# GP_ESP32_Circuit_Sheet.net
KiCad netlist of a schematic drawn in Altium Designer
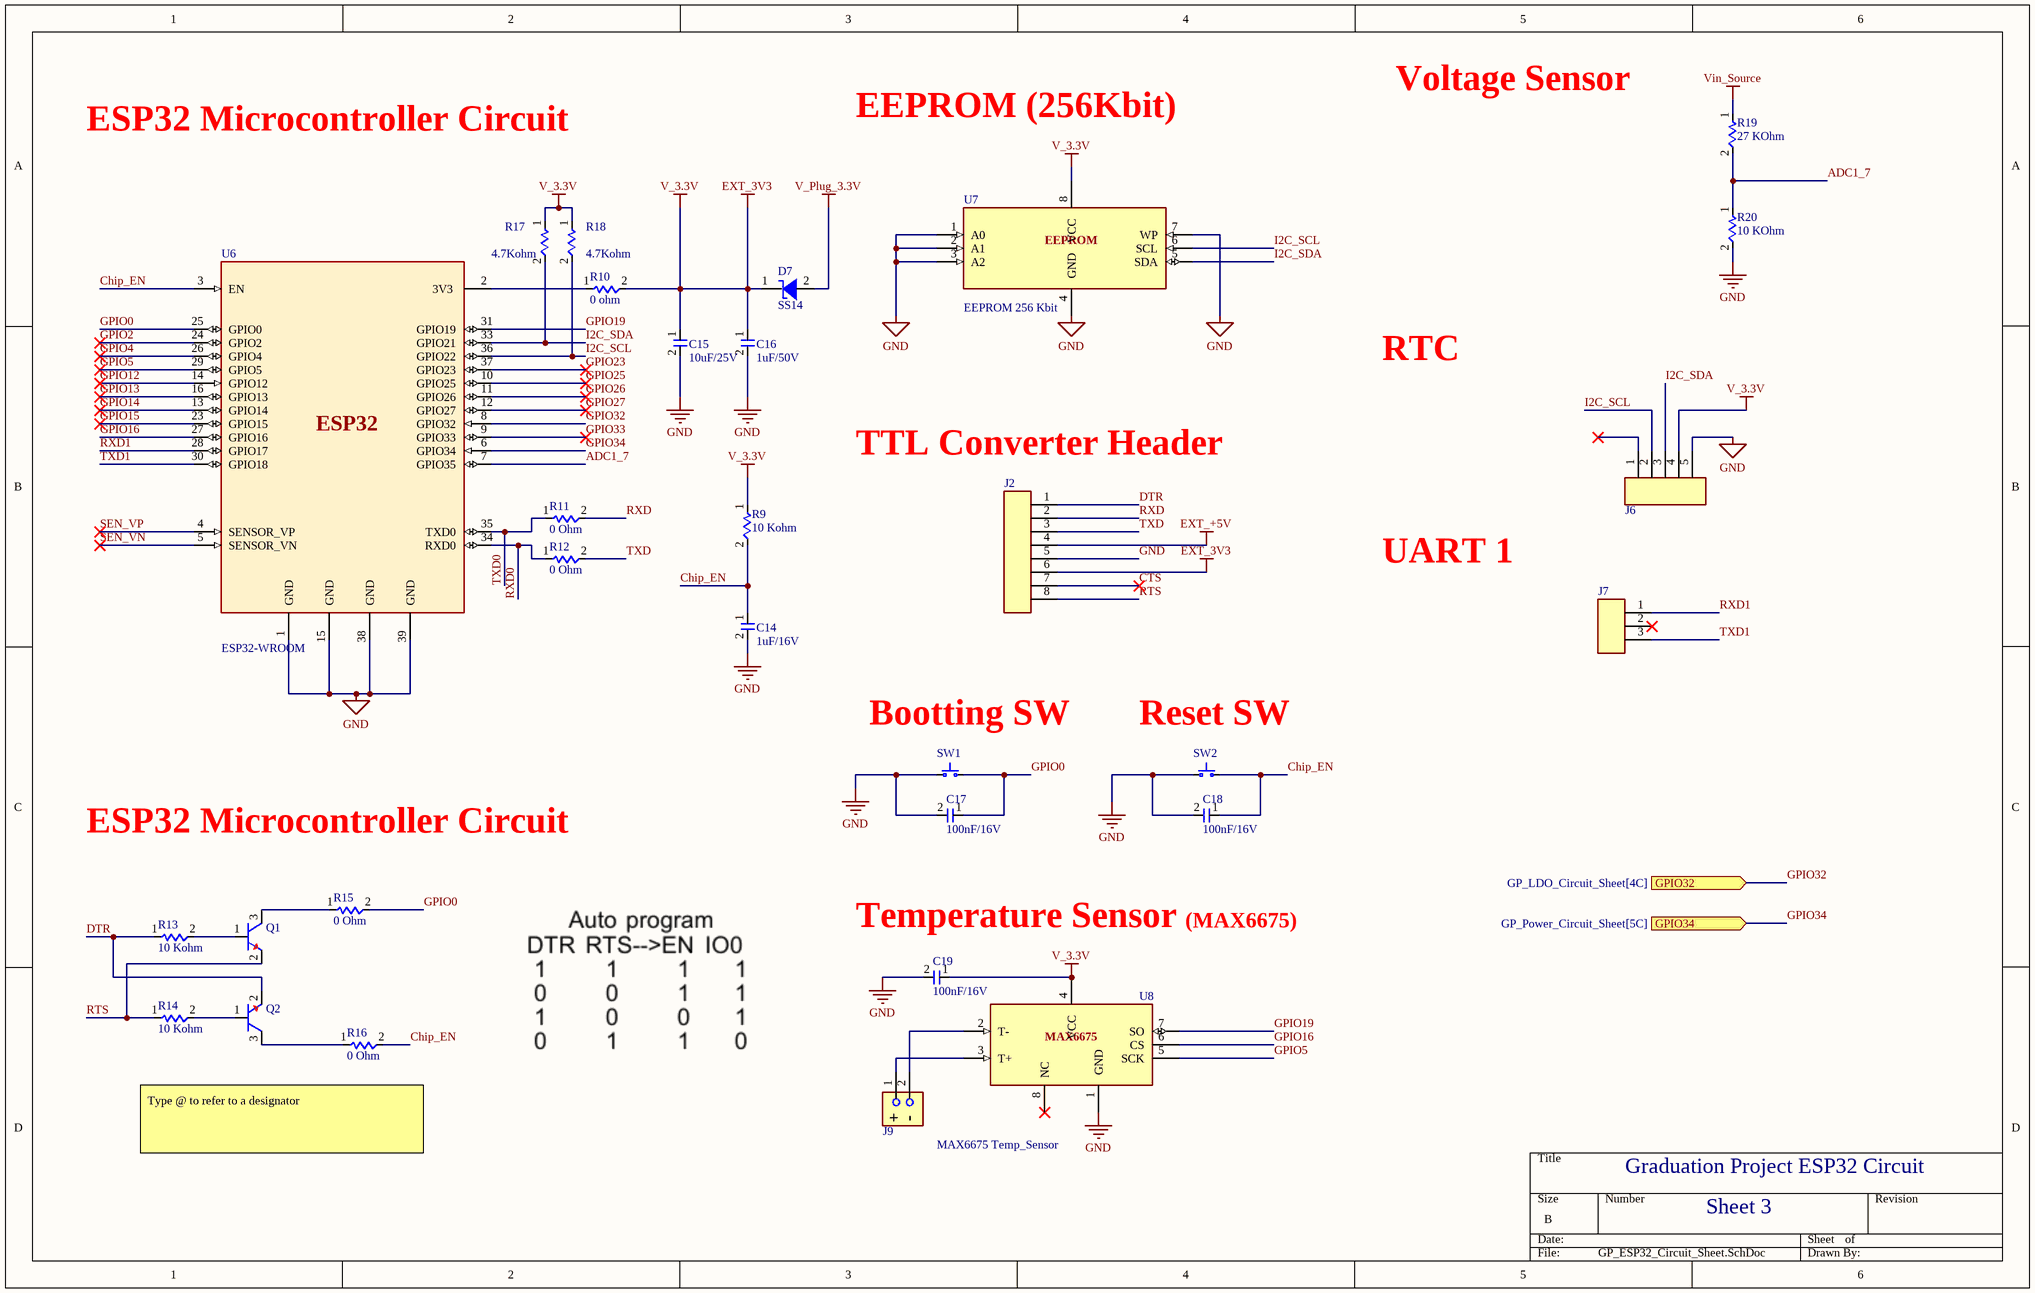
[diagram p0: GP_ESP32_Circuit_Sheet.SchDoc]

(export (version "E")
  (design (tool "Eeschema 10.0.6"))
  (components
    (comp (ref "C14")
      (value "1uF/16V")
      (footprint "Capacitor 100nF")
      (description "Ceramic Capacitor (100nF , 50V) SMD (1206)")
      (libsource (lib "GP_Integrated_Library") (part "Capacitor 100nF"))
    )
    (comp (ref "C15")
      (value "10uF/25V")
      (footprint "Capacitor 100nF")
      (description "Ceramic Capacitor (100nF , 50V) SMD (1206)")
      (libsource (lib "GP_Integrated_Library") (part "Capacitor 100nF"))
    )
    (comp (ref "C16")
      (value "1uF/50V")
      (footprint "Capacitor 100nF")
      (description "Ceramic Capacitor (100nF , 50V) SMD (1206)")
      (libsource (lib "GP_Integrated_Library") (part "Capacitor 100nF"))
    )
    (comp (ref "C17")
      (value "100nF/16V")
      (footprint "Capacitor 100nF")
      (description "Ceramic Capacitor (100nF , 50V) SMD (1206)")
      (libsource (lib "GP_Integrated_Library") (part "Capacitor 100nF"))
    )
    (comp (ref "C18")
      (value "100nF/16V")
      (footprint "Capacitor 100nF")
      (description "Ceramic Capacitor (100nF , 50V) SMD (1206)")
      (libsource (lib "GP_Integrated_Library") (part "Capacitor 100nF"))
    )
    (comp (ref "C19")
      (value "100nF/16V")
      (footprint "Capacitor 100nF")
      (description "Ceramic Capacitor (100nF , 50V) SMD (1206)")
      (libsource (lib "GP_Integrated_Library") (part "Capacitor 100nF"))
    )
    (comp (ref "D7")
      (value "SS14")
      (footprint "Schottky SS14")
      (description "SMD Schottky diode 5A 40V 1N5824 SS54 DO-214AB SMC")
      (libsource (lib "GP_Integrated_Library") (part "Schottky SS14"))
    )
    (comp (ref "J2")
      (value "Pin Header 1x8")
      (footprint "Pin Header 1x8")
      (description "Pin Header male (2.54mm) 1X40 Straight Long (20 CM)")
      (libsource (lib "GP_Integrated_Library") (part "Pin Header 1x8"))
    )
    (comp (ref "J6")
      (value "Pin Header 1x5")
      (footprint "Header Pin 1x5")
      (description "Pin Header male (2.54mm) 1X40 Straight Long (20 CM)")
      (libsource (lib "GP_Integrated_Library") (part "Pin Header 1x5"))
    )
    (comp (ref "J7")
      (value "Pin Header 1x2")
      (footprint "Header Pin 1x3")
      (description "Pin Header male (2.54mm) 1X40 Straight Long (20 CM)")
      (libsource (lib "GP_Integrated_Library") (part "Pin Header 1x2"))
    )
    (comp (ref "J9")
      (value "terminal block connector")
      (footprint "Battery Connector")
      (description "2-Pole 5mm Pitch PCB Mount Screw TermInal Block 8A 250V")
      (libsource (lib "GP_Integrated_Library") (part "Terminal Block"))
    )
    (comp (ref "Q1")
      (value "Transistor npn")
      (footprint "Transistor npn")
      (description "0.6A , 75V , NPN General Purpose Transistor .(SOT-23)")
      (libsource (lib "GP_Integrated_Library") (part "Transistor npn"))
    )
    (comp (ref "Q2")
      (value "Transistor npn")
      (footprint "Transistor npn")
      (description "0.6A , 75V , NPN General Purpose Transistor .(SOT-23)")
      (libsource (lib "GP_Integrated_Library") (part "Transistor npn"))
    )
    (comp (ref "R9")
      (value "10 Kohm")
      (footprint "Resistor 4.7KKohm")
      (description "SMD RESISTORS 200V-500V 1206 ? 5% tolerance")
      (libsource (lib "GP_Integrated_Library") (part "Resistor 10 Kohm"))
    )
    (comp (ref "R10")
      (value "0 ohm")
      (footprint "Resistor 4.7KKohm")
      (description "SMD Resistor (220 ohm , 1/4W)")
      (libsource (lib "GP_Integrated_Library") (part "Resistor 4.7Kohm"))
    )
    (comp (ref "R11")
      (value "0 Ohm")
      (footprint "Resistor 0.050ohm")
      (description "2512 SMD Alloy Power Shunt Resistors 1W 6.4×3.2mm 0.050 Ohm ( SMD Marking R050)")
      (libsource (lib "GP_Integrated_Library") (part "Resistor 0.050 Ohm"))
    )
    (comp (ref "R12")
      (value "0 Ohm")
      (footprint "Resistor 0.050ohm")
      (description "2512 SMD Alloy Power Shunt Resistors 1W 6.4×3.2mm 0.050 Ohm ( SMD Marking R050)")
      (libsource (lib "GP_Integrated_Library") (part "Resistor 0.050 Ohm"))
    )
    (comp (ref "R13")
      (value "10 Kohm")
      (footprint "Resistor 4.7KKohm")
      (description "SMD RESISTORS 200V-500V 1206 ? 5% tolerance")
      (libsource (lib "GP_Integrated_Library") (part "Resistor 10 Kohm"))
    )
    (comp (ref "R14")
      (value "10 Kohm")
      (footprint "Resistor 4.7KKohm")
      (description "SMD RESISTORS 200V-500V 1206 ? 5% tolerance")
      (libsource (lib "GP_Integrated_Library") (part "Resistor 10 Kohm"))
    )
    (comp (ref "R15")
      (value "0 Ohm")
      (footprint "Resistor 0.050ohm")
      (description "2512 SMD Alloy Power Shunt Resistors 1W 6.4×3.2mm 0.050 Ohm ( SMD Marking R050)")
      (libsource (lib "GP_Integrated_Library") (part "Resistor 0.050 Ohm"))
    )
    (comp (ref "R16")
      (value "0 Ohm")
      (footprint "Resistor 0.050ohm")
      (description "2512 SMD Alloy Power Shunt Resistors 1W 6.4×3.2mm 0.050 Ohm ( SMD Marking R050)")
      (libsource (lib "GP_Integrated_Library") (part "Resistor 0.050 Ohm"))
    )
    (comp (ref "R17")
      (value "4.7Kohm")
      (footprint "Resistor 4.7KKohm")
      (description "SMD Resistor (220 ohm , 1/4W)")
      (libsource (lib "GP_Integrated_Library") (part "Resistor 4.7Kohm"))
    )
    (comp (ref "R18")
      (value "4.7Kohm")
      (footprint "Resistor 4.7KKohm")
      (description "SMD Resistor (220 ohm , 1/4W)")
      (libsource (lib "GP_Integrated_Library") (part "Resistor 4.7Kohm"))
    )
    (comp (ref "R19")
      (value "27 KOhm")
      (footprint "Resistor 0.050ohm")
      (description "2512 SMD Alloy Power Shunt Resistors 1W 6.4×3.2mm 0.050 Ohm ( SMD Marking R050)")
      (libsource (lib "GP_Integrated_Library") (part "Resistor 0.050 Ohm"))
    )
    (comp (ref "R20")
      (value "10 KOhm")
      (footprint "Resistor 0.050ohm")
      (description "2512 SMD Alloy Power Shunt Resistors 1W 6.4×3.2mm 0.050 Ohm ( SMD Marking R050)")
      (libsource (lib "GP_Integrated_Library") (part "Resistor 0.050 Ohm"))
    )
    (comp (ref "SW1")
      (value "Push Button")
      (footprint "Push Button")
      (description "PCB Press 2pin (6X6) 100K cycles\r\nMomentary Push Button Tact Tactile Switch")
      (libsource (lib "GP_Integrated_Library") (part "Push Button"))
    )
    (comp (ref "SW2")
      (value "Push Button")
      (footprint "Push Button")
      (description "PCB Press 2pin (6X6) 100K cycles\r\nMomentary Push Button Tact Tactile Switch")
      (libsource (lib "GP_Integrated_Library") (part "Push Button"))
    )
    (comp (ref "U6")
      (value "ESP32-WROOM")
      (footprint "ESP32")
      (description "Bluetooth, WiFi 802.11b/g/n, Bluetooth v5.0 Transceiver Module 2.4GHz PCB Trace Surface Mount")
      (libsource (lib "GP_Integrated_Library") (part "ESP32-WROOM"))
    )
    (comp (ref "U7")
      (value "EEPROM 256 Kbit")
      (footprint "EEPROM")
      (description "I2C-Compatible, (2-Wire) Serial EEPROM 256-Kbit (32,768 x 8).(SOIC-8)")
      (libsource (lib "GP_Integrated_Library") (part "EEPROM 256 Kbit"))
    )
    (comp (ref "U8")
      (value "MAX6675 Temp_Sensor")
      (footprint "MAX6675")
      (description "Cold-Junction-Compensated K-Thermocoupleto-Digital Converter (0?C to +1024?C).(SO-8)")
      (libsource (lib "GP_Integrated_Library") (part "MAX6675 Temp_Sensor"))
    )
  )
  (nets
    (net (code "2") (name "/ADC1_7") (class "Default")
      (node (ref "R19") (pin "2") (pinfunction "pin_2_2") (pintype "passive"))
      (node (ref "R20") (pin "1") (pinfunction "Pin_1_1") (pintype "passive"))
      (node (ref "U6") (pin "7") (pinfunction "GPIO35_7") (pintype "bidirectional"))
    )
    (net (code "3") (name "/CTS") (class "Default")
      (node (ref "J2") (pin "7") (pinfunction "7_7") (pintype "passive+no_connect"))
    )
    (net (code "4") (name "/Chip_EN") (class "Default")
      (node (ref "C14") (pin "1") (pinfunction "Pin_1_1") (pintype "passive"))
      (node (ref "C18") (pin "1") (pinfunction "Pin_1_1") (pintype "passive"))
      (node (ref "R16") (pin "2") (pinfunction "pin_2_2") (pintype "passive"))
      (node (ref "R9") (pin "2") (pinfunction "pin_2_2") (pintype "passive"))
      (node (ref "SW2") (pin "2") (pintype "passive"))
      (node (ref "U6") (pin "3") (pinfunction "EN_3") (pintype "input"))
    )
    (net (code "5") (name "/DTR") (class "Default")
      (node (ref "J2") (pin "1") (pinfunction "1_1") (pintype "passive"))
      (node (ref "Q2") (pin "2") (pinfunction "2_2") (pintype "passive"))
      (node (ref "R13") (pin "1") (pinfunction "Pin_1_1") (pintype "passive"))
    )
    (net (code "6") (name "/GPIO0") (class "Default")
      (node (ref "C17") (pin "1") (pinfunction "Pin_1_1") (pintype "passive"))
      (node (ref "R15") (pin "2") (pinfunction "pin_2_2") (pintype "passive"))
      (node (ref "SW1") (pin "2") (pintype "passive"))
      (node (ref "U6") (pin "25") (pinfunction "GPIO0_25") (pintype "bidirectional"))
    )
    (net (code "7") (name "/GPIO2") (class "Default")
      (node (ref "U6") (pin "24") (pinfunction "GPIO2_24") (pintype "bidirectional+no_connect"))
    )
    (net (code "8") (name "/GPIO4") (class "Default")
      (node (ref "U6") (pin "26") (pinfunction "GPIO4_26") (pintype "bidirectional+no_connect"))
    )
    (net (code "9") (name "/GPIO5") (class "Default")
      (node (ref "U6") (pin "29") (pinfunction "GPIO5_29") (pintype "bidirectional"))
      (node (ref "U8") (pin "5") (pinfunction "SCK_5") (pintype "passive"))
    )
    (net (code "10") (name "/GPIO12") (class "Default")
      (node (ref "U6") (pin "14") (pinfunction "GPIO12_14") (pintype "input+no_connect"))
    )
    (net (code "11") (name "/GPIO13") (class "Default")
      (node (ref "U6") (pin "16") (pinfunction "GPIO13_16") (pintype "bidirectional+no_connect"))
    )
    (net (code "12") (name "/GPIO14") (class "Default")
      (node (ref "U6") (pin "13") (pinfunction "GPIO14_13") (pintype "bidirectional+no_connect"))
    )
    (net (code "13") (name "/GPIO15") (class "Default")
      (node (ref "U6") (pin "23") (pinfunction "GPIO15_23") (pintype "bidirectional+no_connect"))
    )
    (net (code "14") (name "/GPIO16") (class "Default")
      (node (ref "U6") (pin "27") (pinfunction "GPIO16_27") (pintype "bidirectional"))
      (node (ref "U8") (pin "6") (pinfunction "CS_6") (pintype "passive"))
    )
    (net (code "15") (name "/GPIO19") (class "Default")
      (node (ref "U6") (pin "31") (pinfunction "GPIO19_31") (pintype "bidirectional"))
      (node (ref "U8") (pin "7") (pinfunction "SO_7") (pintype "bidirectional"))
    )
    (net (code "16") (name "/GPIO23") (class "Default")
      (node (ref "U6") (pin "37") (pinfunction "GPIO23_37") (pintype "bidirectional+no_connect"))
    )
    (net (code "17") (name "/GPIO25") (class "Default")
      (node (ref "U6") (pin "10") (pinfunction "GPIO25_10") (pintype "bidirectional+no_connect"))
    )
    (net (code "18") (name "/GPIO26") (class "Default")
      (node (ref "U6") (pin "11") (pinfunction "GPIO26_11") (pintype "bidirectional+no_connect"))
    )
    (net (code "19") (name "/GPIO27") (class "Default")
      (node (ref "U6") (pin "12") (pinfunction "GPIO27_12") (pintype "bidirectional+no_connect"))
    )
    (net (code "20") (name "/GPIO32") (class "Default")
      (node (ref "U6") (pin "8") (pinfunction "GPIO32_8") (pintype "input"))
    )
    (net (code "21") (name "/GPIO33") (class "Default")
      (node (ref "U6") (pin "9") (pinfunction "GPIO33_9") (pintype "bidirectional+no_connect"))
    )
    (net (code "22") (name "/GPIO34") (class "Default")
      (node (ref "U6") (pin "6") (pinfunction "GPIO34_6") (pintype "input"))
    )
    (net (code "23") (name "/I2C_SCL") (class "Default")
      (node (ref "J6") (pin "2") (pinfunction "2_2") (pintype "passive"))
      (node (ref "R18") (pin "2") (pinfunction "pin_2_2") (pintype "passive"))
      (node (ref "U6") (pin "36") (pinfunction "GPIO22_36") (pintype "bidirectional"))
      (node (ref "U7") (pin "6") (pinfunction "SCL_6") (pintype "input"))
    )
    (net (code "24") (name "/I2C_SDA") (class "Default")
      (node (ref "J6") (pin "3") (pinfunction "3_3") (pintype "passive"))
      (node (ref "R17") (pin "2") (pinfunction "pin_2_2") (pintype "passive"))
      (node (ref "U6") (pin "33") (pinfunction "GPIO21_33") (pintype "bidirectional"))
      (node (ref "U7") (pin "5") (pinfunction "SDA_5") (pintype "bidirectional"))
    )
    (net (code "25") (name "/RTS") (class "Default")
      (node (ref "J2") (pin "8") (pinfunction "8_8") (pintype "passive"))
      (node (ref "Q1") (pin "2") (pinfunction "2_2") (pintype "passive"))
      (node (ref "R14") (pin "1") (pinfunction "Pin_1_1") (pintype "passive"))
    )
    (net (code "26") (name "/RXD") (class "Default")
      (node (ref "J2") (pin "2") (pinfunction "2_2") (pintype "passive"))
      (node (ref "R11") (pin "2") (pinfunction "pin_2_2") (pintype "passive"))
    )
    (net (code "27") (name "/RXD0") (class "Default")
      (node (ref "R12") (pin "1") (pinfunction "Pin_1_1") (pintype "passive"))
      (node (ref "U6") (pin "34") (pinfunction "RXD0_34") (pintype "bidirectional"))
    )
    (net (code "28") (name "/RXD1") (class "Default")
      (node (ref "J7") (pin "1") (pinfunction "1_1") (pintype "passive"))
      (node (ref "U6") (pin "28") (pinfunction "GPIO17_28") (pintype "bidirectional"))
    )
    (net (code "29") (name "/SEN_VN") (class "Default")
      (node (ref "U6") (pin "5") (pinfunction "SENSOR_VN_5") (pintype "input+no_connect"))
    )
    (net (code "30") (name "/SEN_VP") (class "Default")
      (node (ref "U6") (pin "4") (pinfunction "SENSOR_VP_4") (pintype "input+no_connect"))
    )
    (net (code "31") (name "/TXD") (class "Default")
      (node (ref "J2") (pin "3") (pinfunction "3_3") (pintype "passive"))
      (node (ref "R12") (pin "2") (pinfunction "pin_2_2") (pintype "passive"))
    )
    (net (code "32") (name "/TXD0") (class "Default")
      (node (ref "R11") (pin "1") (pinfunction "Pin_1_1") (pintype "passive"))
      (node (ref "U6") (pin "35") (pinfunction "TXD0_35") (pintype "bidirectional"))
    )
    (net (code "33") (name "/TXD1") (class "Default")
      (node (ref "J7") (pin "3") (pinfunction "3_3") (pintype "passive"))
      (node (ref "U6") (pin "30") (pinfunction "GPIO18_30") (pintype "bidirectional"))
    )
    (net (code "34") (name "EXT_+5V") (class "Default")
      (node (ref "J2") (pin "4") (pinfunction "4_4") (pintype "passive"))
    )
    (net (code "35") (name "EXT_3V3") (class "Default")
      (node (ref "C15") (pin "1") (pinfunction "Pin_1_1") (pintype "passive"))
      (node (ref "C16") (pin "1") (pinfunction "Pin_1_1") (pintype "passive"))
      (node (ref "C19") (pin "1") (pinfunction "Pin_1_1") (pintype "passive"))
      (node (ref "D7") (pin "1") (pintype "passive"))
      (node (ref "J2") (pin "6") (pinfunction "6_6") (pintype "passive"))
      (node (ref "J6") (pin "4") (pinfunction "4_4") (pintype "passive"))
      (node (ref "R10") (pin "2") (pinfunction "pin_2_2") (pintype "passive"))
      (node (ref "R17") (pin "1") (pinfunction "Pin_1_1") (pintype "passive"))
      (node (ref "R18") (pin "1") (pinfunction "Pin_1_1") (pintype "passive"))
      (node (ref "R9") (pin "1") (pinfunction "Pin_1_1") (pintype "passive"))
      (node (ref "U7") (pin "8") (pinfunction "VCC_8") (pintype "power_in"))
      (node (ref "U8") (pin "4") (pinfunction "VCC_4") (pintype "power_in"))
    )
    (net (code "36") (name "GND") (class "Default")
      (node (ref "C14") (pin "2") (pinfunction "Pin_2_2") (pintype "passive"))
      (node (ref "C15") (pin "2") (pinfunction "Pin_2_2") (pintype "passive"))
      (node (ref "C16") (pin "2") (pinfunction "Pin_2_2") (pintype "passive"))
      (node (ref "C17") (pin "2") (pinfunction "Pin_2_2") (pintype "passive"))
      (node (ref "C18") (pin "2") (pinfunction "Pin_2_2") (pintype "passive"))
      (node (ref "C19") (pin "2") (pinfunction "Pin_2_2") (pintype "passive"))
      (node (ref "J2") (pin "5") (pinfunction "5_5") (pintype "passive"))
      (node (ref "J6") (pin "5") (pinfunction "5_5") (pintype "passive"))
      (node (ref "R20") (pin "2") (pinfunction "pin_2_2") (pintype "passive"))
      (node (ref "SW1") (pin "1") (pintype "passive"))
      (node (ref "SW2") (pin "1") (pintype "passive"))
      (node (ref "U6") (pin "1") (pinfunction "GND_1") (pintype "power_in"))
      (node (ref "U6") (pin "15") (pinfunction "GND_15") (pintype "power_in"))
      (node (ref "U6") (pin "38") (pinfunction "GND_38") (pintype "power_in"))
      (node (ref "U6") (pin "39") (pinfunction "GND_39") (pintype "power_in"))
      (node (ref "U7") (pin "1") (pinfunction "A0_1") (pintype "input"))
      (node (ref "U7") (pin "2") (pinfunction "A1_2") (pintype "input"))
      (node (ref "U7") (pin "3") (pinfunction "A2_3") (pintype "input"))
      (node (ref "U7") (pin "4") (pinfunction "GND_4") (pintype "power_in"))
      (node (ref "U7") (pin "7") (pinfunction "WP_7") (pintype "input"))
      (node (ref "U8") (pin "1") (pinfunction "GND_1") (pintype "power_in"))
    )
    (net (code "37") (name "Net-(R10-Pin_1)") (class "Default")
      (node (ref "R10") (pin "1") (pinfunction "Pin_1_1") (pintype "passive"))
      (node (ref "U6") (pin "2") (pinfunction "3V3_2") (pintype "power_in"))
    )
    (net (code "38") (name "Net-(R13-pin_2)") (class "Default")
      (node (ref "Q1") (pin "1") (pinfunction "1_1") (pintype "passive"))
      (node (ref "R13") (pin "2") (pinfunction "pin_2_2") (pintype "passive"))
    )
    (net (code "39") (name "Net-(R14-pin_2)") (class "Default")
      (node (ref "Q2") (pin "1") (pinfunction "1_1") (pintype "passive"))
      (node (ref "R14") (pin "2") (pinfunction "pin_2_2") (pintype "passive"))
    )
    (net (code "40") (name "Net-(R15-Pin_1)") (class "Default")
      (node (ref "Q1") (pin "3") (pinfunction "3_3") (pintype "passive"))
      (node (ref "R15") (pin "1") (pinfunction "Pin_1_1") (pintype "passive"))
    )
    (net (code "41") (name "Net-(R16-Pin_1)") (class "Default")
      (node (ref "Q2") (pin "3") (pinfunction "3_3") (pintype "passive"))
      (node (ref "R16") (pin "1") (pinfunction "Pin_1_1") (pintype "passive"))
    )
    (net (code "42") (name "Net-(U8-T+)") (class "Default")
      (node (ref "J9") (pin "1") (pinfunction "2_1") (pintype "passive"))
      (node (ref "U8") (pin "3") (pinfunction "T+_3") (pintype "input"))
    )
    (net (code "43") (name "Net-(U8-T-)") (class "Default")
      (node (ref "J9") (pin "2") (pinfunction "2_2") (pintype "passive"))
      (node (ref "U8") (pin "2") (pinfunction "T-_2") (pintype "input"))
    )
    (net (code "44") (name "V_Plug_3.3V") (class "Default") (node (ref "D7") (pin "2") (pintype "passive")))
    (net (code "45") (name "Vin_Source") (class "Default")
      (node (ref "R19") (pin "1") (pinfunction "Pin_1_1") (pintype "passive"))
    )
    (net (code "46") (name "unconnected-(J6-Pad1)") (class "Default")
      (node (ref "J6") (pin "1") (pinfunction "1_1") (pintype "passive+no_connect"))
    )
    (net (code "47") (name "unconnected-(J7-Pad2)") (class "Default")
      (node (ref "J7") (pin "2") (pinfunction "2_2") (pintype "passive+no_connect"))
    )
    (net (code "48") (name "unconnected-(U8-NC-Pad8)") (class "Default")
      (node (ref "U8") (pin "8") (pinfunction "NC_8") (pintype "passive+no_connect"))
    )
  )
)
